# Light_Siren.net
KiCad netlist of a schematic drawn in EAGLE
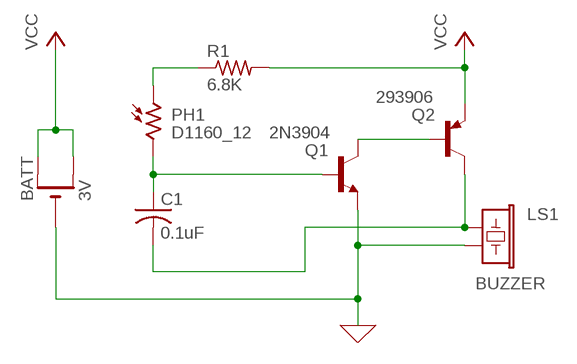
[diagram p0: schematic, sheet 1]

(export (version "E")
  (design (tool "Eeschema 10.0.6"))
  (components
    (comp (ref "BATT")
      (value "3V")
      (footprint "eagle-import:CR1220-THM")
      (libsource (lib "eagle-import") (part "CR1220THM"))
    )
    (comp (ref "C1")
      (value "0.1uF")
      (footprint "eagle-import:C025-025X050")
      (libsource (lib "eagle-import") (part "C-US025-025X050"))
    )
    (comp (ref "LS1")
      (value "BUZZER")
      (footprint "eagle-import:BUZZER-12MM-NS")
      (libsource (lib "eagle-import") (part "BUZZER-PTH_NO_SILK"))
    )
    (comp (ref "PH1")
      (value "D1160_12")
      (footprint "eagle-import:D11XX")
      (libsource (lib "eagle-import") (part "D1160_12"))
    )
    (comp (ref "Q1")
      (value "2N3904")
      (footprint "eagle-import:TO92")
      (libsource (lib "eagle-import") (part "-NPN-TO92"))
    )
    (comp (ref "Q2")
      (value "293906")
      (footprint "eagle-import:TO92")
      (libsource (lib "eagle-import") (part "-PNP-TO92"))
    )
    (comp (ref "R1")
      (value "6.8K")
      (footprint "eagle-import:0207_10")
      (libsource (lib "eagle-import") (part "R-US_0207/10"))
    )
  )
  (nets
    (net (code "1") (name "GND") (class "Default")
      (node (ref "BATT") (pin "-") (pinfunction "-_-") (pintype "passive"))
      (node (ref "LS1") (pin "-") (pinfunction "2_-") (pintype "passive"))
      (node (ref "Q1") (pin "1") (pinfunction "E_1") (pintype "passive"))
    )
    (net (code "2") (name "Net-(LS1-1)") (class "Default")
      (node (ref "C1") (pin "2") (pinfunction "2_2") (pintype "passive"))
      (node (ref "LS1") (pin "+") (pinfunction "1_+") (pintype "passive"))
      (node (ref "Q2") (pin "3") (pinfunction "C_3") (pintype "passive"))
    )
    (net (code "3") (name "Net-(PH1-Pad1)") (class "Default")
      (node (ref "PH1") (pin "1") (pinfunction "1_1") (pintype "passive"))
      (node (ref "R1") (pin "1") (pinfunction "1_1") (pintype "passive"))
    )
    (net (code "4") (name "Net-(Q1-B)") (class "Default")
      (node (ref "C1") (pin "1") (pinfunction "1_1") (pintype "passive"))
      (node (ref "PH1") (pin "2") (pinfunction "2_2") (pintype "passive"))
      (node (ref "Q1") (pin "2") (pinfunction "B_2") (pintype "passive"))
    )
    (net (code "5") (name "Net-(Q1-C)") (class "Default")
      (node (ref "Q1") (pin "3") (pinfunction "C_3") (pintype "passive"))
      (node (ref "Q2") (pin "2") (pinfunction "B_2") (pintype "passive"))
    )
    (net (code "6") (name "VCC") (class "Default")
      (node (ref "BATT") (pin "+1") (pinfunction "+_+1") (pintype "passive"))
      (node (ref "BATT") (pin "+2") (pinfunction "+1_+2") (pintype "passive"))
      (node (ref "Q2") (pin "1") (pinfunction "E_1") (pintype "passive"))
      (node (ref "R1") (pin "2") (pinfunction "2_2") (pintype "passive"))
    )
  )
)
